# zmod4410.net
KiCad netlist of a schematic drawn in EAGLE
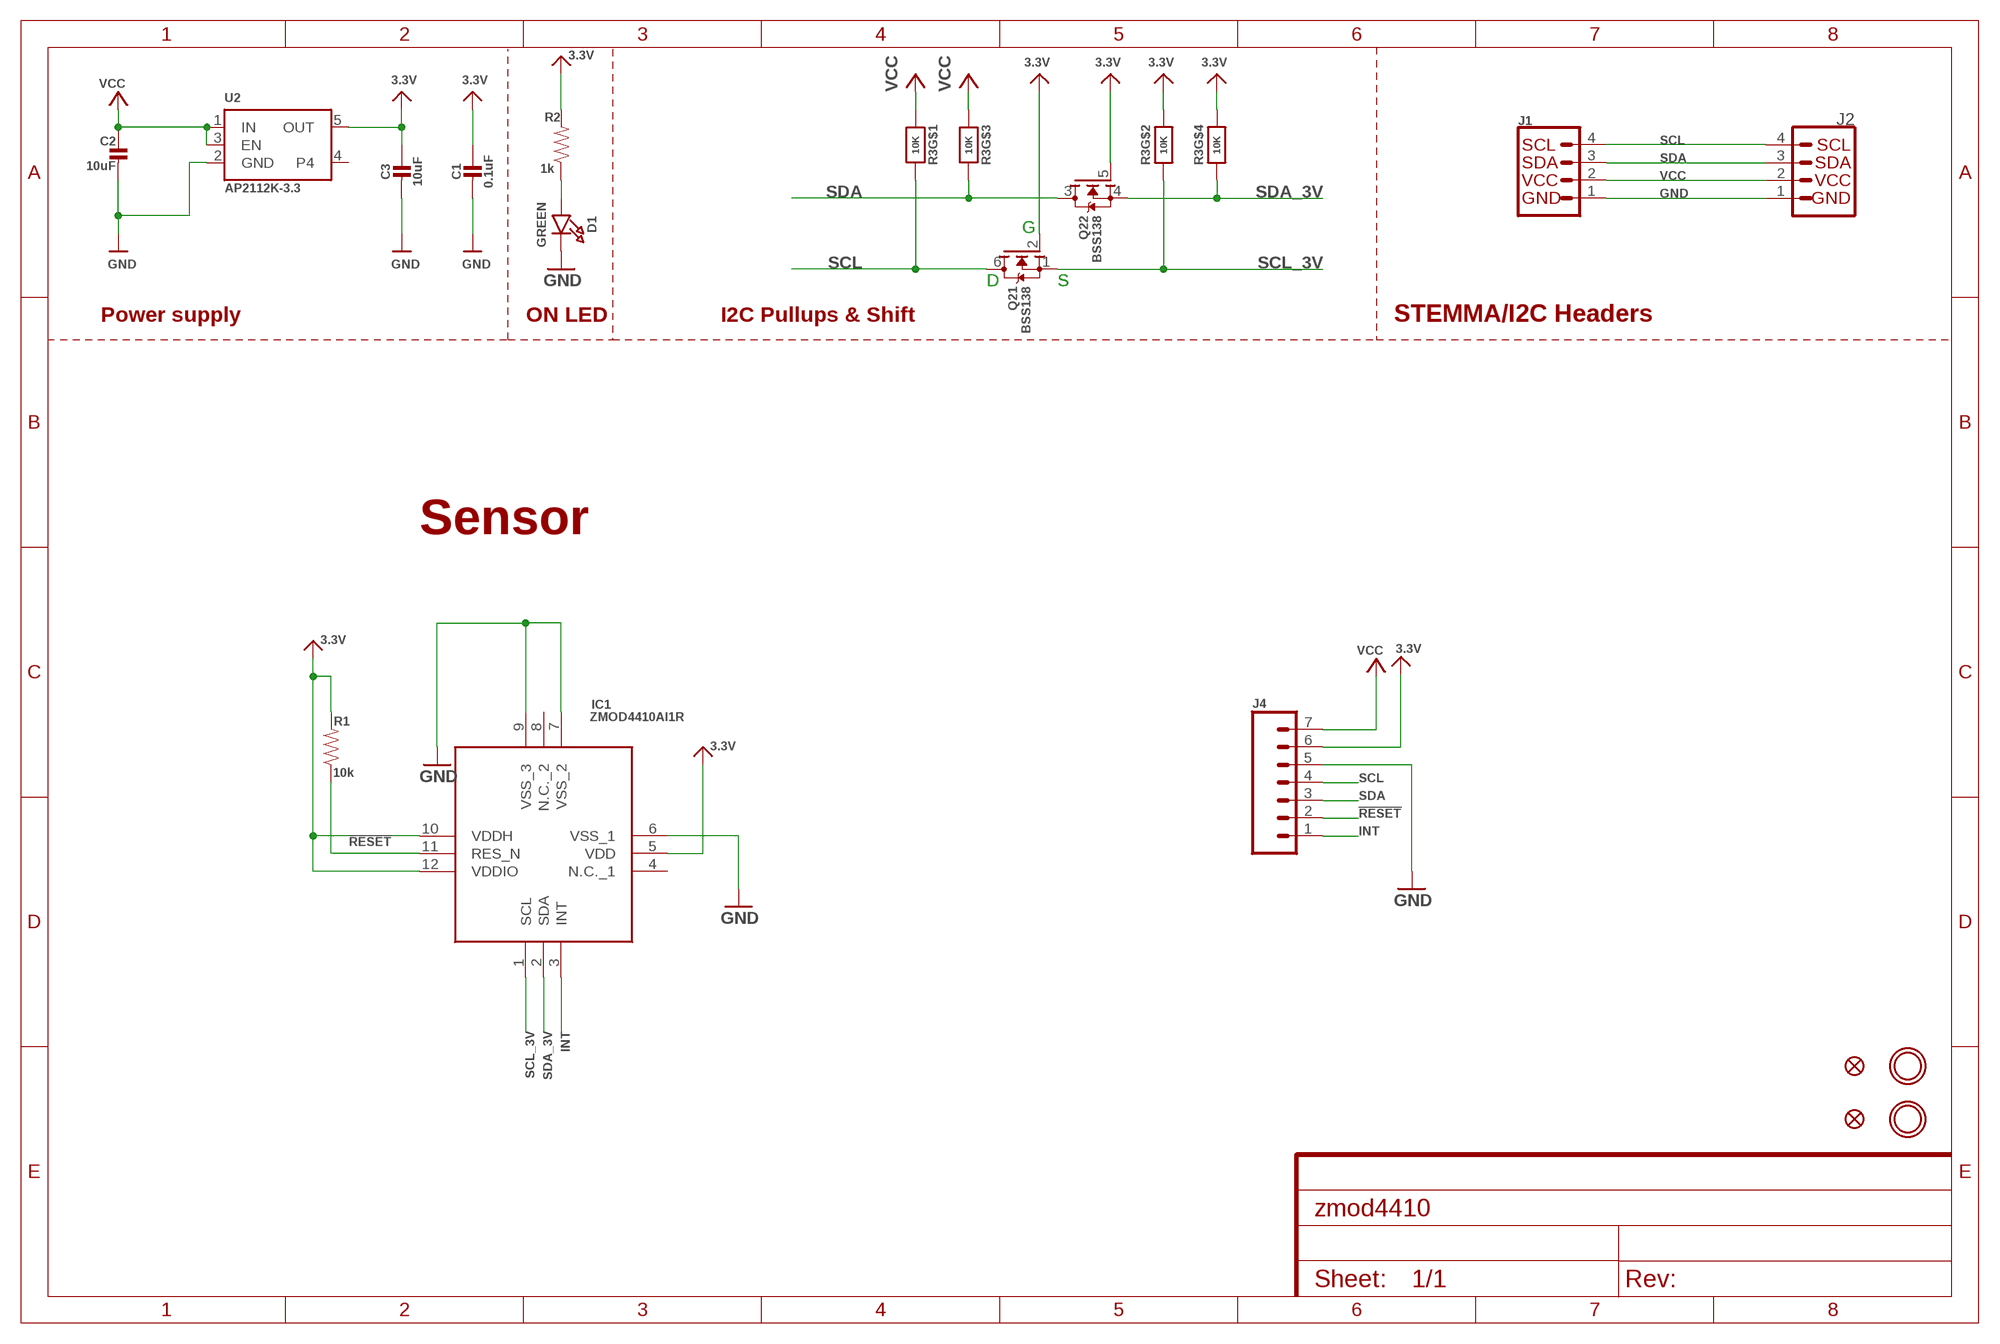
[diagram p0: schematic, sheet 1]

(export (version "E")
  (design (tool "Eeschema 10.0.6"))
  (components
    (comp (ref "C1")
      (value "0.1uF")
      (footprint "eagle-import:0603-NO")
      (libsource (lib "eagle-import") (part "CAP_CERAMIC0603_NO"))
    )
    (comp (ref "C2")
      (value "10uF")
      (footprint "eagle-import:0805-NO")
      (libsource (lib "eagle-import") (part "CAP_CERAMIC0805-NOOUTLINE"))
    )
    (comp (ref "C3")
      (value "10uF")
      (footprint "eagle-import:0805-NO")
      (libsource (lib "eagle-import") (part "CAP_CERAMIC0805-NOOUTLINE"))
    )
    (comp (ref "D1")
      (value "GREEN")
      (footprint "eagle-import:CHIPLED_0603_NOOUTLINE")
      (libsource (lib "eagle-import") (part "LED0603_NOOUTLINE"))
    )
    (comp (ref "FID3")
      (value "FIDUCIAL_1MM")
      (footprint "eagle-import:FIDUCIAL_1MM")
      (libsource (lib "eagle-import") (part "FIDUCIAL_1MM"))
    )
    (comp (ref "FID4")
      (value "FIDUCIAL_1MM")
      (footprint "eagle-import:FIDUCIAL_1MM")
      (libsource (lib "eagle-import") (part "FIDUCIAL_1MM"))
    )
    (comp (ref "GND")
      (value "MOUNTINGHOLE2.5")
      (footprint "eagle-import:MOUNTINGHOLE_2.5_PLATED")
      (libsource (lib "eagle-import") (part "MOUNTINGHOLE2.5"))
    )
    (comp (ref "IC1")
      (value "ZMOD4410AI1R")
      (footprint "eagle-import:ZMOD4410AI1R")
      (fields (field (name "MOUSER_PART_NUMBER") "964-ZMOD4410AI1R"))
      (libsource (lib "eagle-import") (part "ZMOD4410AI1R"))
    )
    (comp (ref "J1")
      (value "QWIIC_CONNECTORJS-1MM")
      (footprint "eagle-import:1X04_1MM_RA")
      (libsource (lib "eagle-import") (part "QWIIC_CONNECTORJS-1MM"))
    )
    (comp (ref "J2")
      (value "QWIIC_CONNECTORJS-1MM")
      (footprint "eagle-import:1X04_1MM_RA")
      (libsource (lib "eagle-import") (part "QWIIC_CONNECTORJS-1MM"))
    )
    (comp (ref "J4")
      (value "CONN_07")
      (footprint "eagle-import:1X07")
      (libsource (lib "eagle-import") (part "CONN_07"))
    )
    (comp (ref "Q2")
      (value "BSS138")
      (footprint "eagle-import:SOT363")
      (libsource (lib "eagle-import") (part "MOSFET-N_DUAL"))
    )
    (comp (ref "R1")
      (value "10k")
      (footprint "eagle-import:0603")
      (libsource (lib "eagle-import") (part "1KOHM-0603-1/10W-1%"))
    )
    (comp (ref "R2")
      (value "1k")
      (footprint "eagle-import:0603")
      (libsource (lib "eagle-import") (part "1KOHM-0603-1/10W-1%"))
    )
    (comp (ref "R3")
      (value "10K")
      (footprint "eagle-import:RESPACK_4X0603")
      (libsource (lib "eagle-import") (part "RESISTOR_4PACK"))
    )
    (comp (ref "U$8")
      (value "MOUNTINGHOLE2.5")
      (footprint "eagle-import:MOUNTINGHOLE_2.5_PLATED")
      (libsource (lib "eagle-import") (part "MOUNTINGHOLE2.5"))
    )
    (comp (ref "U2")
      (value "AP2112K-3.3")
      (footprint "eagle-import:SOT23-5")
      (libsource (lib "eagle-import") (part "VREG_SOT23-5"))
    )
  )
  (nets
    (net (code "1") (name "/~{RESET}") (class "Default")
      (node (ref "IC1") (pin "11") (pinfunction "RES_N_11") (pintype "bidirectional"))
      (node (ref "J4") (pin "2") (pinfunction "2_2") (pintype "passive"))
      (node (ref "R1") (pin "1") (pinfunction "1_1") (pintype "passive"))
    )
    (net (code "2") (name "3.3V") (class "Default")
      (node (ref "C1") (pin "1") (pinfunction "1_1") (pintype "passive"))
      (node (ref "C3") (pin "1") (pinfunction "1_1") (pintype "passive"))
      (node (ref "IC1") (pin "10") (pinfunction "VDDH_10") (pintype "bidirectional"))
      (node (ref "IC1") (pin "12") (pinfunction "VDDIO_12") (pintype "bidirectional"))
      (node (ref "IC1") (pin "5") (pinfunction "VDD_5") (pintype "bidirectional"))
      (node (ref "J4") (pin "6") (pinfunction "6_6") (pintype "passive"))
      (node (ref "Q2") (pin "2") (pinfunction "G_2") (pintype "bidirectional"))
      (node (ref "Q2") (pin "5") (pinfunction "G_5") (pintype "bidirectional"))
      (node (ref "R1") (pin "2") (pinfunction "2_2") (pintype "passive"))
      (node (ref "R2") (pin "2") (pinfunction "2_2") (pintype "passive"))
      (node (ref "R3") (pin "2") (pinfunction "1_2") (pintype "passive"))
      (node (ref "R3") (pin "4") (pinfunction "1_4") (pintype "passive"))
      (node (ref "U2") (pin "5") (pinfunction "OUT_5") (pintype "power_in"))
    )
    (net (code "3") (name "GND") (class "Default")
      (node (ref "C1") (pin "2") (pinfunction "2_2") (pintype "passive"))
      (node (ref "C2") (pin "2") (pinfunction "2_2") (pintype "passive"))
      (node (ref "C3") (pin "2") (pinfunction "2_2") (pintype "passive"))
      (node (ref "D1") (pin "C") (pinfunction "C_C") (pintype "passive"))
      (node (ref "IC1") (pin "6") (pinfunction "VSS_1_6") (pintype "bidirectional"))
      (node (ref "IC1") (pin "7") (pinfunction "VSS_2_7") (pintype "bidirectional"))
      (node (ref "IC1") (pin "9") (pinfunction "VSS_3_9") (pintype "bidirectional"))
      (node (ref "J1") (pin "1") (pinfunction "1_1") (pintype "power_in"))
      (node (ref "J2") (pin "1") (pinfunction "1_1") (pintype "power_in"))
      (node (ref "J4") (pin "5") (pinfunction "5_5") (pintype "passive"))
      (node (ref "U2") (pin "2") (pinfunction "GND_2") (pintype "power_in"))
    )
    (net (code "4") (name "INT") (class "Default")
      (node (ref "IC1") (pin "3") (pinfunction "INT_3") (pintype "bidirectional"))
      (node (ref "J4") (pin "1") (pinfunction "1_1") (pintype "passive"))
    )
    (net (code "5") (name "Net-(D1-PadA)") (class "Default")
      (node (ref "D1") (pin "A") (pinfunction "A_A") (pintype "passive"))
      (node (ref "R2") (pin "1") (pinfunction "1_1") (pintype "passive"))
    )
    (net (code "6") (name "SCL") (class "Default")
      (node (ref "J1") (pin "4") (pinfunction "4_4") (pintype "passive"))
      (node (ref "J2") (pin "4") (pinfunction "4_4") (pintype "passive"))
      (node (ref "J4") (pin "4") (pinfunction "4_4") (pintype "passive"))
      (node (ref "Q2") (pin "6") (pinfunction "D_6") (pintype "bidirectional"))
      (node (ref "R3") (pin "8") (pinfunction "2_8") (pintype "passive"))
    )
    (net (code "7") (name "SCL_3V") (class "Default")
      (node (ref "IC1") (pin "1") (pinfunction "SCL_1") (pintype "bidirectional"))
      (node (ref "Q2") (pin "1") (pinfunction "S_1") (pintype "bidirectional"))
      (node (ref "R3") (pin "7") (pinfunction "2_7") (pintype "passive"))
    )
    (net (code "8") (name "SDA") (class "Default")
      (node (ref "J1") (pin "3") (pinfunction "3_3") (pintype "passive"))
      (node (ref "J2") (pin "3") (pinfunction "3_3") (pintype "passive"))
      (node (ref "J4") (pin "3") (pinfunction "3_3") (pintype "passive"))
      (node (ref "Q2") (pin "3") (pinfunction "D_3") (pintype "bidirectional"))
      (node (ref "R3") (pin "6") (pinfunction "2_6") (pintype "passive"))
    )
    (net (code "9") (name "SDA_3V") (class "Default")
      (node (ref "IC1") (pin "2") (pinfunction "SDA_2") (pintype "bidirectional"))
      (node (ref "Q2") (pin "4") (pinfunction "S_4") (pintype "bidirectional"))
      (node (ref "R3") (pin "5") (pinfunction "2_5") (pintype "passive"))
    )
    (net (code "10") (name "VCC") (class "Default")
      (node (ref "C2") (pin "1") (pinfunction "1_1") (pintype "passive"))
      (node (ref "J1") (pin "2") (pinfunction "2_2") (pintype "power_in"))
      (node (ref "J2") (pin "2") (pinfunction "2_2") (pintype "power_in"))
      (node (ref "J4") (pin "7") (pinfunction "7_7") (pintype "passive"))
      (node (ref "R3") (pin "1") (pinfunction "1_1") (pintype "passive"))
      (node (ref "R3") (pin "3") (pinfunction "1_3") (pintype "passive"))
      (node (ref "U2") (pin "1") (pinfunction "IN_1") (pintype "power_in"))
      (node (ref "U2") (pin "3") (pinfunction "EN_3") (pintype "input"))
    )
    (net (code "11") (name "unconnected-(IC1-N.C._1-Pad4)") (class "Default")
      (node (ref "IC1") (pin "4") (pinfunction "N.C._1_4") (pintype "bidirectional"))
    )
    (net (code "12") (name "unconnected-(IC1-N.C._2-Pad8)") (class "Default")
      (node (ref "IC1") (pin "8") (pinfunction "N.C._2_8") (pintype "bidirectional"))
    )
    (net (code "13") (name "unconnected-(U2-P4-Pad4)") (class "Default")
      (node (ref "U2") (pin "4") (pinfunction "P4_4") (pintype "bidirectional"))
    )
  )
)
